# driver_piezo2.net
KiCad netlist of a schematic drawn in EAGLE
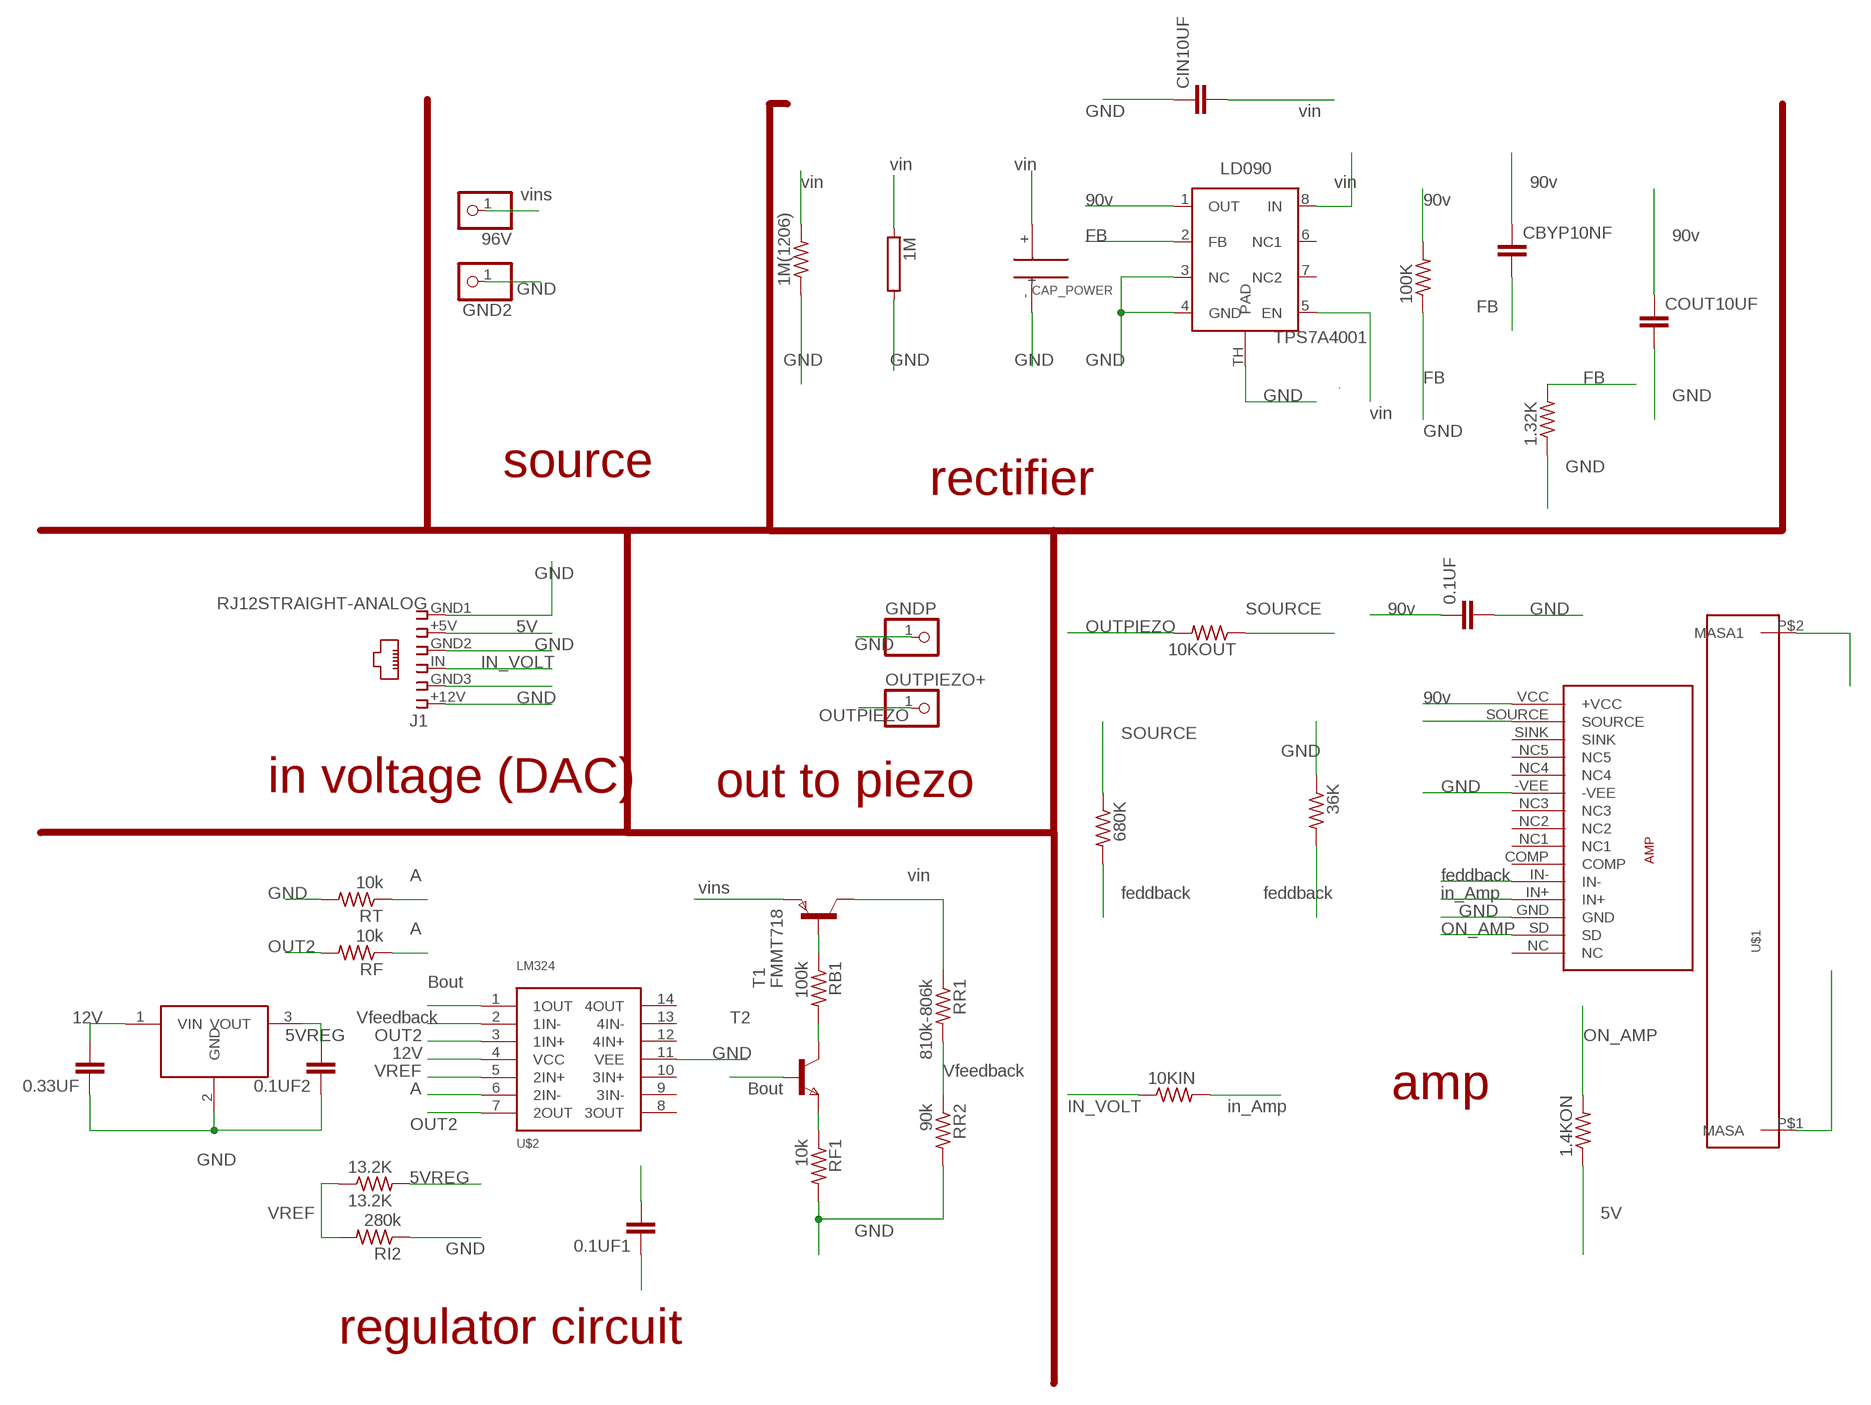
[diagram p0: schematic, sheet 1]

(export (version "E")
  (design (tool "Eeschema 10.0.6"))
  (components
    (comp (ref "0.1UF")
      (value "C-EUC1206")
      (footprint "eagle-import:C1206")
      (libsource (lib "eagle-import") (part "C-EUC1206"))
    )
    (comp (ref "0.1UF1")
      (value "C-EUC1206")
      (footprint "eagle-import:C1206")
      (libsource (lib "eagle-import") (part "C-EUC1206"))
    )
    (comp (ref "0.1UF2")
      (value "C-EUC1206")
      (footprint "eagle-import:C1206")
      (libsource (lib "eagle-import") (part "C-EUC1206"))
    )
    (comp (ref "0.33UF")
      (value "C-EUC1206")
      (footprint "eagle-import:C1206")
      (libsource (lib "eagle-import") (part "C-EUC1206"))
    )
    (comp (ref "1.4KON")
      (value "R-US_R1206")
      (footprint "eagle-import:R1206")
      (libsource (lib "eagle-import") (part "R-US_R1206"))
    )
    (comp (ref "1.32K")
      (value "R-US_R1206")
      (footprint "eagle-import:R1206")
      (libsource (lib "eagle-import") (part "R-US_R1206"))
    )
    (comp (ref "1M")
      (value "RCA0002")
      (footprint "eagle-import:CA0002")
      (libsource (lib "eagle-import") (part "RCA0002"))
    )
    (comp (ref "1M(1206)")
      (value "R-US_R1206")
      (footprint "eagle-import:R1206")
      (libsource (lib "eagle-import") (part "R-US_R1206"))
    )
    (comp (ref "10KIN")
      (value "R-US_R1206")
      (footprint "eagle-import:R1206")
      (libsource (lib "eagle-import") (part "R-US_R1206"))
    )
    (comp (ref "10KOUT")
      (value "R-US_R1206")
      (footprint "eagle-import:R1206")
      (libsource (lib "eagle-import") (part "R-US_R1206"))
    )
    (comp (ref "13.2K")
      (value "13.2K")
      (footprint "eagle-import:R1206")
      (libsource (lib "eagle-import") (part "R-US_R1206"))
    )
    (comp (ref "36K")
      (value "R-US_R1206")
      (footprint "eagle-import:R1206")
      (libsource (lib "eagle-import") (part "R-US_R1206"))
    )
    (comp (ref "96V")
      (value "PINHD-1X1")
      (footprint "eagle-import:1X01")
      (libsource (lib "eagle-import") (part "PINHD-1X1"))
    )
    (comp (ref "100K")
      (value "R-US_R1206")
      (footprint "eagle-import:R1206")
      (libsource (lib "eagle-import") (part "R-US_R1206"))
    )
    (comp (ref "680K")
      (value "R-US_R1206")
      (footprint "eagle-import:R1206")
      (libsource (lib "eagle-import") (part "R-US_R1206"))
    )
    (comp (ref "AMP")
      (value "POWER_AMP_LME49811TB")
      (footprint "eagle-import:POWER_AMP_LME49811TB")
      (libsource (lib "eagle-import") (part "POWER_AMP_LME49811TB"))
    )
    (comp (ref "CAP_POWER")
      (value "CAP200VCAP200V")
      (footprint "eagle-import:CAP200V")
      (libsource (lib "eagle-import") (part "CAP200VCAP200V"))
    )
    (comp (ref "CBYP10NF")
      (value "C-EUC1206")
      (footprint "eagle-import:C1206")
      (libsource (lib "eagle-import") (part "C-EUC1206"))
    )
    (comp (ref "CIN10UF")
      (value "C-EUC1206")
      (footprint "eagle-import:C1206")
      (libsource (lib "eagle-import") (part "C-EUC1206"))
    )
    (comp (ref "COUT10UF")
      (value "C-EUC1206")
      (footprint "eagle-import:C1206")
      (libsource (lib "eagle-import") (part "C-EUC1206"))
    )
    (comp (ref "GND2")
      (value "PINHD-1X1")
      (footprint "eagle-import:1X01")
      (libsource (lib "eagle-import") (part "PINHD-1X1"))
    )
    (comp (ref "GNDP")
      (value "PINHD-1X1")
      (footprint "eagle-import:1X01")
      (libsource (lib "eagle-import") (part "PINHD-1X1"))
    )
    (comp (ref "J1")
      (value "RJ12STRAIGHT-ANALOG")
      (footprint "eagle-import:RJ12-STRAIGHT-ANALOG")
      (libsource (lib "eagle-import") (part "RJ12STRAIGHT-ANALOG"))
    )
    (comp (ref "LD090")
      (value "TPS7A4001")
      (footprint "eagle-import:S-PDSO-G08")
      (libsource (lib "eagle-import") (part "TPS7A4001"))
    )
    (comp (ref "OUTPIEZO+")
      (value "PINHD-1X1")
      (footprint "eagle-import:1X01")
      (libsource (lib "eagle-import") (part "PINHD-1X1"))
    )
    (comp (ref "RB1")
      (value "100k")
      (footprint "eagle-import:R1206")
      (libsource (lib "eagle-import") (part "R-US_R1206"))
    )
    (comp (ref "RF")
      (value "10k")
      (footprint "eagle-import:R1206")
      (libsource (lib "eagle-import") (part "R-US_R1206"))
    )
    (comp (ref "RF1")
      (value "10k")
      (footprint "eagle-import:R1206")
      (libsource (lib "eagle-import") (part "R-US_R1206"))
    )
    (comp (ref "RI2")
      (value "280k")
      (footprint "eagle-import:R1206")
      (libsource (lib "eagle-import") (part "R-US_R1206"))
    )
    (comp (ref "RR1")
      (value "810k-806k")
      (footprint "eagle-import:R1206")
      (libsource (lib "eagle-import") (part "R-US_R1206"))
    )
    (comp (ref "RR2")
      (value "90k")
      (footprint "eagle-import:R1206")
      (libsource (lib "eagle-import") (part "R-US_R1206"))
    )
    (comp (ref "RT")
      (value "10k")
      (footprint "eagle-import:R1206")
      (libsource (lib "eagle-import") (part "R-US_R1206"))
    )
    (comp (ref "T1")
      (value "FMMT718")
      (footprint "eagle-import:SOT-23")
      (libsource (lib "eagle-import") (part "FMMT718"))
    )
    (comp (ref "T2")
      (value "NPNSOT89")
      (footprint "eagle-import:SOT89")
      (fields (field (name "MPN") "DSS4540X-13"))
      (libsource (lib "eagle-import") (part "NPNSOT89"))
    )
    (comp (ref "U$1")
      (value "DISIPADOR")
      (footprint "eagle-import:DISIPADOR")
      (libsource (lib "eagle-import") (part "DISIPADOR"))
    )
    (comp (ref "U$2")
      (value "LM324")
      (footprint "eagle-import:SO14")
      (libsource (lib "eagle-import") (part "LM324"))
    )
    (comp (ref "U$3")
      (value "7805")
      (footprint "eagle-import:TO220")
      (libsource (lib "eagle-import") (part "7805"))
    )
  )
  (nets
    (net (code "1") (name "/1OUT") (class "Default")
      (node (ref "T2") (pin "1") (pinfunction "B_1") (pintype "passive"))
      (node (ref "U$2") (pin "1") (pinfunction "1OUT_1") (pintype "bidirectional"))
    )
    (net (code "2") (name "/2IN+") (class "Default")
      (node (ref "13.2K") (pin "1") (pinfunction "1_1") (pintype "passive"))
      (node (ref "RI2") (pin "2") (pinfunction "2_2") (pintype "passive"))
      (node (ref "U$2") (pin "5") (pinfunction "2IN+_5") (pintype "bidirectional"))
    )
    (net (code "3") (name "/2IN-") (class "Default")
      (node (ref "RF") (pin "1") (pinfunction "1_1") (pintype "passive"))
      (node (ref "RT") (pin "1") (pinfunction "1_1") (pintype "passive"))
      (node (ref "U$2") (pin "6") (pinfunction "2IN-_6") (pintype "bidirectional"))
    )
    (net (code "4") (name "/2OUT") (class "Default")
      (node (ref "RF") (pin "2") (pinfunction "2_2") (pintype "passive"))
      (node (ref "U$2") (pin "3") (pinfunction "1IN+_3") (pintype "bidirectional"))
      (node (ref "U$2") (pin "7") (pinfunction "2OUT_7") (pintype "bidirectional"))
    )
    (net (code "5") (name "/5V") (class "Default")
      (node (ref "1.4KON") (pin "1") (pinfunction "1_1") (pintype "passive"))
      (node (ref "J1") (pin "+5V") (pinfunction "5_+5V") (pintype "bidirectional"))
    )
    (net (code "6") (name "/5VOP") (class "Default")
      (node (ref "0.1UF2") (pin "2") (pinfunction "2_2") (pintype "passive"))
      (node (ref "13.2K") (pin "2") (pinfunction "2_2") (pintype "passive"))
      (node (ref "U$3") (pin "3") (pinfunction "VOUT_3") (pintype "bidirectional"))
    )
    (net (code "7") (name "/12V") (class "Default")
      (node (ref "0.1UF1") (pin "2") (pinfunction "2_2") (pintype "passive"))
      (node (ref "0.33UF") (pin "2") (pinfunction "2_2") (pintype "passive"))
      (node (ref "J1") (pin "+12V") (pinfunction "1_+12V") (pintype "bidirectional"))
      (node (ref "U$2") (pin "4") (pinfunction "VCC_4") (pintype "bidirectional"))
      (node (ref "U$3") (pin "1") (pinfunction "VIN_1") (pintype "bidirectional"))
    )
    (net (code "8") (name "/B") (class "Default")
      (node (ref "36K") (pin "2") (pinfunction "2_2") (pintype "passive"))
      (node (ref "680K") (pin "2") (pinfunction "2_2") (pintype "passive"))
      (node (ref "AMP") (pin "IN-") (pinfunction "IN-_IN-") (pintype "bidirectional"))
    )
    (net (code "9") (name "/FB") (class "Default")
      (node (ref "1.32K") (pin "2") (pinfunction "2_2") (pintype "passive"))
      (node (ref "100K") (pin "1") (pinfunction "1_1") (pintype "passive"))
      (node (ref "CBYP10NF") (pin "2") (pinfunction "2_2") (pintype "passive"))
      (node (ref "LD090") (pin "2") (pinfunction "FB_2") (pintype "passive"))
    )
    (net (code "10") (name "/GND") (class "Default")
      (node (ref "0.1UF") (pin "2") (pinfunction "2_2") (pintype "passive"))
      (node (ref "0.1UF1") (pin "1") (pinfunction "1_1") (pintype "passive"))
      (node (ref "0.1UF2") (pin "1") (pinfunction "1_1") (pintype "passive"))
      (node (ref "0.33UF") (pin "1") (pinfunction "1_1") (pintype "passive"))
      (node (ref "1.32K") (pin "1") (pinfunction "1_1") (pintype "passive"))
      (node (ref "1M") (pin "2") (pinfunction "2_2") (pintype "passive"))
      (node (ref "1M(1206)") (pin "1") (pinfunction "1_1") (pintype "passive"))
      (node (ref "36K") (pin "1") (pinfunction "1_1") (pintype "passive"))
      (node (ref "AMP") (pin "-VEE") (pinfunction "-VEE_-VEE") (pintype "bidirectional"))
      (node (ref "AMP") (pin "GND") (pinfunction "GND_GND") (pintype "bidirectional"))
      (node (ref "CAP_POWER") (pin "-") (pinfunction "-_-") (pintype "bidirectional"))
      (node (ref "CIN10UF") (pin "1") (pinfunction "1_1") (pintype "passive"))
      (node (ref "COUT10UF") (pin "2") (pinfunction "2_2") (pintype "passive"))
      (node (ref "GND2") (pin "1") (pinfunction "1_1") (pintype "passive"))
      (node (ref "GNDP") (pin "1") (pinfunction "1_1") (pintype "passive"))
      (node (ref "J1") (pin "GND1") (pinfunction "6_GND1") (pintype "bidirectional"))
      (node (ref "J1") (pin "GND2") (pinfunction "4_GND2") (pintype "bidirectional"))
      (node (ref "J1") (pin "GND3") (pinfunction "2_GND3") (pintype "bidirectional"))
      (node (ref "LD090") (pin "3") (pinfunction "NC_3") (pintype "input"))
      (node (ref "LD090") (pin "4") (pinfunction "GND_4") (pintype "power_in"))
      (node (ref "LD090") (pin "TH") (pinfunction "PAD_TH") (pintype "bidirectional"))
      (node (ref "RF1") (pin "2") (pinfunction "2_2") (pintype "passive"))
      (node (ref "RI2") (pin "1") (pinfunction "1_1") (pintype "passive"))
      (node (ref "RR2") (pin "2") (pinfunction "2_2") (pintype "passive"))
      (node (ref "RT") (pin "2") (pinfunction "2_2") (pintype "passive"))
      (node (ref "U$1") (pin "P$1") (pinfunction "MASA_P$1") (pintype "bidirectional"))
      (node (ref "U$1") (pin "P$2") (pinfunction "MASA1_P$2") (pintype "bidirectional"))
      (node (ref "U$2") (pin "11") (pinfunction "VEE_11") (pintype "bidirectional"))
      (node (ref "U$3") (pin "2") (pinfunction "GND_2") (pintype "bidirectional"))
    )
    (net (code "11") (name "/IN_AMP") (class "Default")
      (node (ref "10KIN") (pin "2") (pinfunction "2_2") (pintype "passive"))
      (node (ref "AMP") (pin "IN+") (pinfunction "IN+_IN+") (pintype "bidirectional"))
    )
    (net (code "12") (name "/IN_VOLTAGE") (class "Default")
      (node (ref "10KIN") (pin "1") (pinfunction "1_1") (pintype "passive"))
      (node (ref "J1") (pin "IN") (pinfunction "3_IN") (pintype "bidirectional"))
    )
    (net (code "13") (name "/ON") (class "Default")
      (node (ref "1.4KON") (pin "2") (pinfunction "2_2") (pintype "passive"))
      (node (ref "AMP") (pin "SD") (pinfunction "SD_SD") (pintype "bidirectional"))
    )
    (net (code "14") (name "/OUT_PIEZO") (class "Default")
      (node (ref "10KOUT") (pin "2") (pinfunction "2_2") (pintype "passive"))
      (node (ref "OUTPIEZO+") (pin "1") (pinfunction "1_1") (pintype "passive"))
    )
    (net (code "15") (name "/SOURCE") (class "Default")
      (node (ref "10KOUT") (pin "1") (pinfunction "1_1") (pintype "passive"))
      (node (ref "680K") (pin "1") (pinfunction "1_1") (pintype "passive"))
      (node (ref "AMP") (pin "SOURCE") (pinfunction "SOURCE_SOURCE") (pintype "bidirectional"))
    )
    (net (code "16") (name "/V90") (class "Default")
      (node (ref "0.1UF") (pin "1") (pinfunction "1_1") (pintype "passive"))
      (node (ref "100K") (pin "2") (pinfunction "2_2") (pintype "passive"))
      (node (ref "AMP") (pin "VCC") (pinfunction "+VCC_VCC") (pintype "bidirectional"))
      (node (ref "CBYP10NF") (pin "1") (pinfunction "1_1") (pintype "passive"))
      (node (ref "COUT10UF") (pin "1") (pinfunction "1_1") (pintype "passive"))
      (node (ref "LD090") (pin "1") (pinfunction "OUT_1") (pintype "input"))
    )
    (net (code "17") (name "/VF") (class "Default")
      (node (ref "RR1") (pin "2") (pinfunction "2_2") (pintype "passive"))
      (node (ref "RR2") (pin "1") (pinfunction "1_1") (pintype "passive"))
      (node (ref "U$2") (pin "2") (pinfunction "1IN-_2") (pintype "bidirectional"))
    )
    (net (code "18") (name "/VIN") (class "Default")
      (node (ref "1M") (pin "1") (pinfunction "1_1") (pintype "passive"))
      (node (ref "1M(1206)") (pin "2") (pinfunction "2_2") (pintype "passive"))
      (node (ref "CAP_POWER") (pin "+") (pinfunction "+_+") (pintype "bidirectional"))
      (node (ref "CIN10UF") (pin "2") (pinfunction "2_2") (pintype "passive"))
      (node (ref "LD090") (pin "5") (pinfunction "EN_5") (pintype "input"))
      (node (ref "LD090") (pin "8") (pinfunction "IN_8") (pintype "input"))
      (node (ref "RR1") (pin "1") (pinfunction "1_1") (pintype "passive"))
      (node (ref "T1") (pin "1") (pinfunction "C_1") (pintype "passive"))
    )
    (net (code "19") (name "/VINS") (class "Default")
      (node (ref "96V") (pin "1") (pinfunction "1_1") (pintype "passive"))
      (node (ref "T1") (pin "2") (pinfunction "E_2") (pintype "passive"))
    )
    (net (code "20") (name "Net-(RB1-Pad2)") (class "Default")
      (node (ref "RB1") (pin "2") (pinfunction "2_2") (pintype "passive"))
      (node (ref "T2") (pin "2") (pinfunction "C_2") (pintype "passive"))
      (node (ref "T2") (pin "2@1") (pinfunction "C_2@1") (pintype "passive"))
    )
    (net (code "21") (name "Net-(T1-B)") (class "Default")
      (node (ref "RB1") (pin "1") (pinfunction "1_1") (pintype "passive"))
      (node (ref "T1") (pin "3") (pinfunction "B_3") (pintype "passive"))
    )
    (net (code "22") (name "Net-(T2-E)") (class "Default")
      (node (ref "RF1") (pin "1") (pinfunction "1_1") (pintype "passive"))
      (node (ref "T2") (pin "3") (pinfunction "E_3") (pintype "passive"))
    )
    (net (code "23") (name "unconnected-(AMP-PadCOMP)") (class "Default")
      (node (ref "AMP") (pin "COMP") (pinfunction "COMP_COMP") (pintype "bidirectional"))
    )
    (net (code "24") (name "unconnected-(AMP-PadNC)") (class "Default")
      (node (ref "AMP") (pin "NC") (pinfunction "NC_NC") (pintype "bidirectional"))
    )
    (net (code "25") (name "unconnected-(AMP-PadNC1)") (class "Default")
      (node (ref "AMP") (pin "NC1") (pinfunction "NC1_NC1") (pintype "bidirectional"))
    )
    (net (code "26") (name "unconnected-(AMP-PadNC2)") (class "Default")
      (node (ref "AMP") (pin "NC2") (pinfunction "NC2_NC2") (pintype "bidirectional"))
    )
    (net (code "27") (name "unconnected-(AMP-PadNC3)") (class "Default")
      (node (ref "AMP") (pin "NC3") (pinfunction "NC3_NC3") (pintype "bidirectional"))
    )
    (net (code "28") (name "unconnected-(AMP-PadNC4)") (class "Default")
      (node (ref "AMP") (pin "NC4") (pinfunction "NC4_NC4") (pintype "bidirectional"))
    )
    (net (code "29") (name "unconnected-(AMP-PadNC5)") (class "Default")
      (node (ref "AMP") (pin "NC5") (pinfunction "NC5_NC5") (pintype "bidirectional"))
    )
    (net (code "30") (name "unconnected-(AMP-PadSINK)") (class "Default")
      (node (ref "AMP") (pin "SINK") (pinfunction "SINK_SINK") (pintype "bidirectional"))
    )
    (net (code "31") (name "unconnected-(LD090-NC1-Pad6)") (class "Default")
      (node (ref "LD090") (pin "6") (pinfunction "NC1_6") (pintype "output"))
    )
    (net (code "32") (name "unconnected-(LD090-NC2-Pad7)") (class "Default")
      (node (ref "LD090") (pin "7") (pinfunction "NC2_7") (pintype "input"))
    )
    (net (code "33") (name "unconnected-(U$2-3IN+-Pad10)") (class "Default")
      (node (ref "U$2") (pin "10") (pinfunction "3IN+_10") (pintype "bidirectional"))
    )
    (net (code "34") (name "unconnected-(U$2-3IN--Pad9)") (class "Default")
      (node (ref "U$2") (pin "9") (pinfunction "3IN-_9") (pintype "bidirectional"))
    )
    (net (code "35") (name "unconnected-(U$2-3OUT-Pad8)") (class "Default")
      (node (ref "U$2") (pin "8") (pinfunction "3OUT_8") (pintype "bidirectional"))
    )
    (net (code "36") (name "unconnected-(U$2-4IN+-Pad12)") (class "Default")
      (node (ref "U$2") (pin "12") (pinfunction "4IN+_12") (pintype "bidirectional"))
    )
    (net (code "37") (name "unconnected-(U$2-4IN--Pad13)") (class "Default")
      (node (ref "U$2") (pin "13") (pinfunction "4IN-_13") (pintype "bidirectional"))
    )
    (net (code "38") (name "unconnected-(U$2-4OUT-Pad14)") (class "Default")
      (node (ref "U$2") (pin "14") (pinfunction "4OUT_14") (pintype "bidirectional"))
    )
  )
)
